# NewBee.net
KiCad netlist of a schematic drawn in Altium Designer
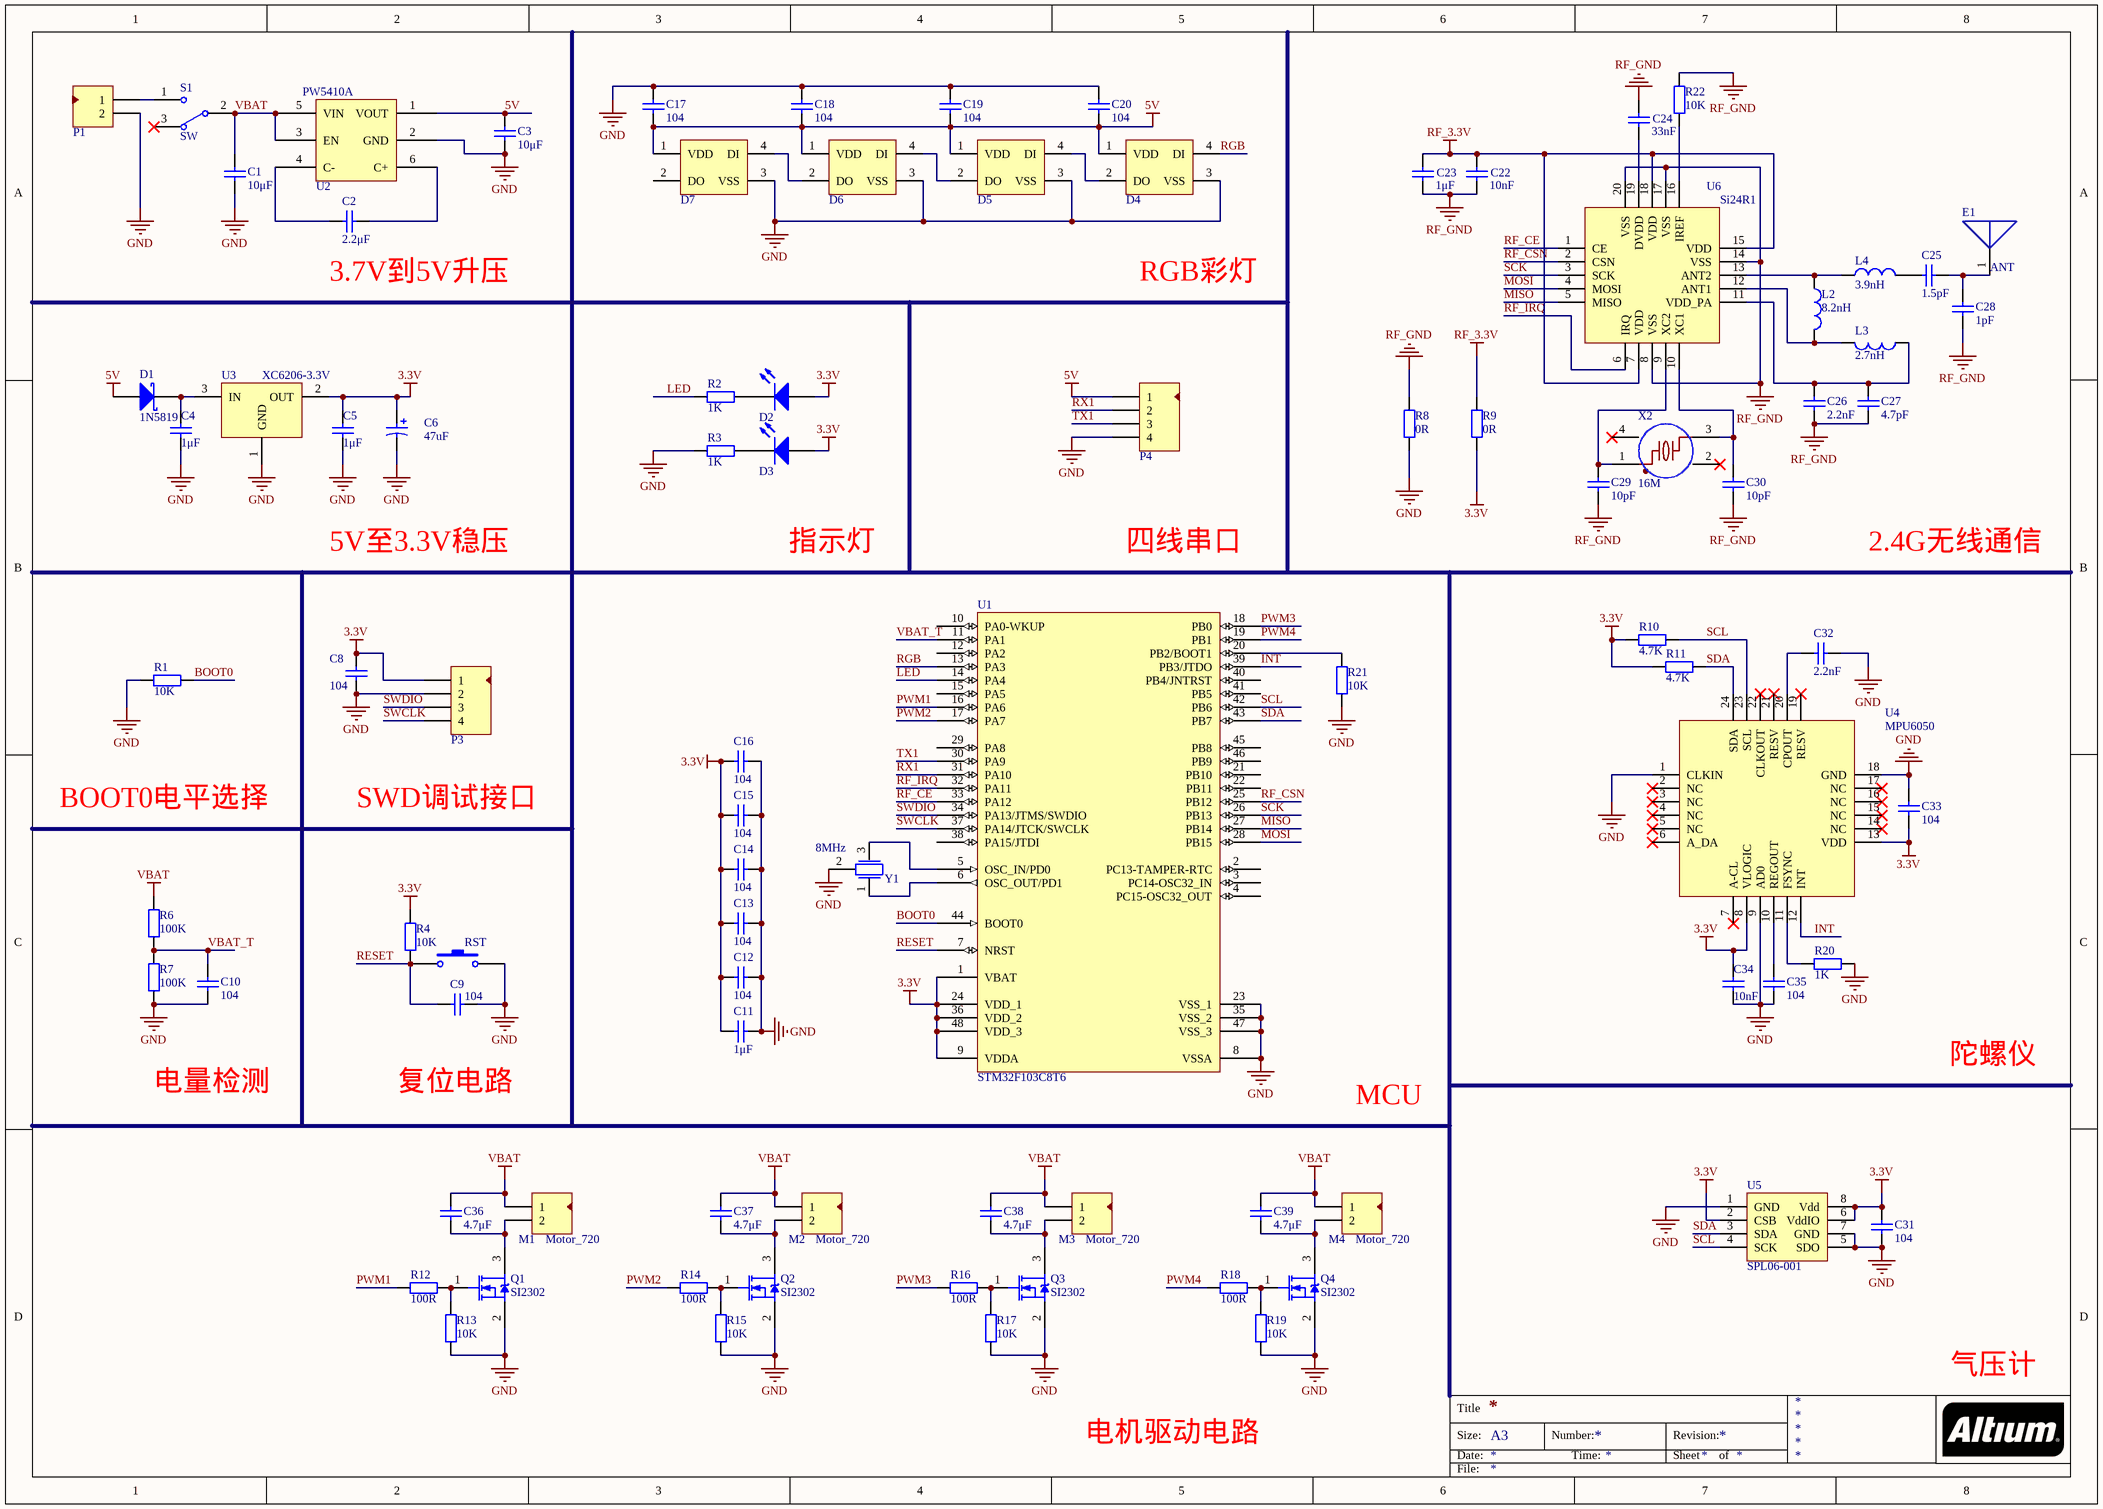
[diagram p0: NewBee.SchDoc]

(export (version "E")
  (design (tool "Eeschema 10.0.6"))
  (components
    (comp (ref "C1")
      (value "10μF")
      (footprint "C-0603")
      (description "贴片瓷片电容")
      (fields (field (name "PUBLISHER") "Altium Limited"))
      (libsource (lib "ChunLee") (part "Cap-S"))
    )
    (comp (ref "C2")
      (value "2.2μF")
      (footprint "C-0603")
      (description "贴片瓷片电容")
      (fields (field (name "PUBLISHER") "Altium Limited"))
      (libsource (lib "ChunLee") (part "Cap-S"))
    )
    (comp (ref "C3")
      (value "10μF")
      (footprint "C-0603")
      (description "贴片瓷片电容")
      (fields (field (name "PUBLISHER") "Altium Limited"))
      (libsource (lib "ChunLee") (part "Cap-S"))
    )
    (comp (ref "C4")
      (value "1μF")
      (footprint "C-0603")
      (description "贴片瓷片电容")
      (fields (field (name "PUBLISHER") "Altium Limited"))
      (libsource (lib "ChunLee") (part "Cap-S"))
    )
    (comp (ref "C5")
      (value "1μF")
      (footprint "C-0603")
      (description "贴片瓷片电容")
      (fields (field (name "PUBLISHER") "Altium Limited"))
      (libsource (lib "ChunLee") (part "Cap-S"))
    )
    (comp (ref "C6")
      (value "47uF")
      (footprint "CAP-3216")
      (description "钽电容")
      (fields (field (name "Comment") "Cap-Pol") (field (name "PUBLISHER") "Altium Limited"))
      (libsource (lib "ChunLee") (part "Cap-Pol-A"))
    )
    (comp (ref "C8")
      (value "104")
      (footprint "C-0603")
      (description "贴片瓷片电容")
      (fields (field (name "PUBLISHER") "Altium Limited"))
      (libsource (lib "ChunLee") (part "Cap-S"))
    )
    (comp (ref "C9")
      (value "104")
      (footprint "C-0603")
      (description "贴片瓷片电容")
      (fields (field (name "PUBLISHER") "Altium Limited"))
      (libsource (lib "ChunLee") (part "Cap-S"))
    )
    (comp (ref "C10")
      (value "104")
      (footprint "C-0603")
      (description "贴片瓷片电容")
      (fields (field (name "PUBLISHER") "Altium Limited"))
      (libsource (lib "ChunLee") (part "Cap-S"))
    )
    (comp (ref "C11")
      (value "1μF")
      (footprint "C-0603")
      (description "贴片瓷片电容")
      (fields (field (name "PUBLISHER") "Altium Limited"))
      (libsource (lib "ChunLee") (part "Cap-S"))
    )
    (comp (ref "C12")
      (value "104")
      (footprint "C-0603")
      (description "贴片瓷片电容")
      (fields (field (name "PUBLISHER") "Altium Limited"))
      (libsource (lib "ChunLee") (part "Cap-S"))
    )
    (comp (ref "C13")
      (value "104")
      (footprint "C-0603")
      (description "贴片瓷片电容")
      (fields (field (name "PUBLISHER") "Altium Limited"))
      (libsource (lib "ChunLee") (part "Cap-S"))
    )
    (comp (ref "C14")
      (value "104")
      (footprint "C-0603")
      (description "贴片瓷片电容")
      (fields (field (name "PUBLISHER") "Altium Limited"))
      (libsource (lib "ChunLee") (part "Cap-S"))
    )
    (comp (ref "C15")
      (value "104")
      (footprint "C-0603")
      (description "贴片瓷片电容")
      (fields (field (name "PUBLISHER") "Altium Limited"))
      (libsource (lib "ChunLee") (part "Cap-S"))
    )
    (comp (ref "C16")
      (value "104")
      (footprint "C-0603")
      (description "贴片瓷片电容")
      (fields (field (name "PUBLISHER") "Altium Limited"))
      (libsource (lib "ChunLee") (part "Cap-S"))
    )
    (comp (ref "C17")
      (value "104")
      (footprint "C-0603")
      (description "贴片瓷片电容")
      (fields (field (name "PUBLISHER") "Altium Limited"))
      (libsource (lib "ChunLee") (part "Cap-S"))
    )
    (comp (ref "C18")
      (value "104")
      (footprint "C-0603")
      (description "贴片瓷片电容")
      (fields (field (name "PUBLISHER") "Altium Limited"))
      (libsource (lib "ChunLee") (part "Cap-S"))
    )
    (comp (ref "C19")
      (value "104")
      (footprint "C-0603")
      (description "贴片瓷片电容")
      (fields (field (name "PUBLISHER") "Altium Limited"))
      (libsource (lib "ChunLee") (part "Cap-S"))
    )
    (comp (ref "C20")
      (value "104")
      (footprint "C-0603")
      (description "贴片瓷片电容")
      (fields (field (name "PUBLISHER") "Altium Limited"))
      (libsource (lib "ChunLee") (part "Cap-S"))
    )
    (comp (ref "C22")
      (value "10nF")
      (footprint "C-0603")
      (description "贴片瓷片电容")
      (fields (field (name "PUBLISHER") "Altium Limited"))
      (libsource (lib "ChunLee") (part "Cap-S"))
    )
    (comp (ref "C23")
      (value "1μF")
      (footprint "C-0603")
      (description "贴片瓷片电容")
      (fields (field (name "PUBLISHER") "Altium Limited"))
      (libsource (lib "ChunLee") (part "Cap-S"))
    )
    (comp (ref "C24")
      (value "33nF")
      (footprint "C-0603")
      (description "贴片瓷片电容")
      (fields (field (name "PUBLISHER") "Altium Limited"))
      (libsource (lib "ChunLee") (part "Cap-S"))
    )
    (comp (ref "C25")
      (value "1.5pF")
      (footprint "C-0603")
      (description "贴片瓷片电容")
      (fields (field (name "PUBLISHER") "Altium Limited"))
      (libsource (lib "ChunLee") (part "Cap-S"))
    )
    (comp (ref "C26")
      (value "2.2nF")
      (footprint "C-0603")
      (description "贴片瓷片电容")
      (fields (field (name "PUBLISHER") "Altium Limited"))
      (libsource (lib "ChunLee") (part "Cap-S"))
    )
    (comp (ref "C27")
      (value "4.7pF")
      (footprint "C-0603")
      (description "贴片瓷片电容")
      (fields (field (name "PUBLISHER") "Altium Limited"))
      (libsource (lib "ChunLee") (part "Cap-S"))
    )
    (comp (ref "C28")
      (value "1pF")
      (footprint "C-0603")
      (description "贴片瓷片电容")
      (fields (field (name "PUBLISHER") "Altium Limited"))
      (libsource (lib "ChunLee") (part "Cap-S"))
    )
    (comp (ref "C29")
      (value "10pF")
      (footprint "C-0603")
      (description "贴片瓷片电容")
      (fields (field (name "PUBLISHER") "Altium Limited"))
      (libsource (lib "ChunLee") (part "Cap-S"))
    )
    (comp (ref "C30")
      (value "10pF")
      (footprint "C-0603")
      (description "贴片瓷片电容")
      (fields (field (name "PUBLISHER") "Altium Limited"))
      (libsource (lib "ChunLee") (part "Cap-S"))
    )
    (comp (ref "C31")
      (value "104")
      (footprint "C-0603")
      (description "贴片瓷片电容")
      (fields (field (name "PUBLISHER") "Altium Limited"))
      (libsource (lib "ChunLee") (part "Cap-S"))
    )
    (comp (ref "C32")
      (value "2.2nF")
      (footprint "C-0603")
      (description "贴片瓷片电容")
      (fields (field (name "PUBLISHER") "Altium Limited"))
      (libsource (lib "ChunLee") (part "Cap-S"))
    )
    (comp (ref "C33")
      (value "104")
      (footprint "C-0603")
      (description "贴片瓷片电容")
      (fields (field (name "PUBLISHER") "Altium Limited"))
      (libsource (lib "ChunLee") (part "Cap-S"))
    )
    (comp (ref "C34")
      (value "10nF")
      (footprint "C-0603")
      (description "贴片瓷片电容")
      (fields (field (name "PUBLISHER") "Altium Limited"))
      (libsource (lib "ChunLee") (part "Cap-S"))
    )
    (comp (ref "C35")
      (value "104")
      (footprint "C-0603")
      (description "贴片瓷片电容")
      (fields (field (name "PUBLISHER") "Altium Limited"))
      (libsource (lib "ChunLee") (part "Cap-S"))
    )
    (comp (ref "C36")
      (value "4.7μF")
      (footprint "C-0603")
      (description "贴片瓷片电容")
      (fields (field (name "PUBLISHER") "Altium Limited"))
      (libsource (lib "ChunLee") (part "Cap-S"))
    )
    (comp (ref "C37")
      (value "4.7μF")
      (footprint "C-0603")
      (description "贴片瓷片电容")
      (fields (field (name "PUBLISHER") "Altium Limited"))
      (libsource (lib "ChunLee") (part "Cap-S"))
    )
    (comp (ref "C38")
      (value "4.7μF")
      (footprint "C-0603")
      (description "贴片瓷片电容")
      (fields (field (name "PUBLISHER") "Altium Limited"))
      (libsource (lib "ChunLee") (part "Cap-S"))
    )
    (comp (ref "C39")
      (value "4.7μF")
      (footprint "C-0603")
      (description "贴片瓷片电容")
      (fields (field (name "PUBLISHER") "Altium Limited"))
      (libsource (lib "ChunLee") (part "Cap-S"))
    )
    (comp (ref "D1")
      (value "1N5819")
      (footprint "SOD-323_L1.6-W1.3-LS2.7-RD")
      (description "肖特基二极管")
      (fields (field (name "TYPE") "1N5819") (field (name "PUBLISHER") "Altium Limited"))
      (libsource (lib "ChunLee") (part "Diode-Schottky"))
    )
    (comp (ref "D2")
      (value "LED0")
      (footprint "LED-0805")
      (description "发光二极管")
      (fields (field (name "PUBLISHER") "Altium Limited"))
      (libsource (lib "ChunLee") (part "LED0"))
    )
    (comp (ref "D3")
      (value "LED0")
      (footprint "LED-0805")
      (description "发光二极管")
      (fields (field (name "PUBLISHER") "Altium Limited"))
      (libsource (lib "ChunLee") (part "LED0"))
    )
    (comp (ref "D4")
      (value "WS2812B")
      (footprint "SMD-5050-4")
      (description "WS2812B 4脚RGB全彩LED")
      (libsource (lib "ChunLee") (part "WS2812B"))
    )
    (comp (ref "D5")
      (value "WS2812B")
      (footprint "SMD-5050-4")
      (description "WS2812B 4脚RGB全彩LED")
      (libsource (lib "ChunLee") (part "WS2812B"))
    )
    (comp (ref "D6")
      (value "WS2812B")
      (footprint "SMD-5050-4")
      (description "WS2812B 4脚RGB全彩LED")
      (libsource (lib "ChunLee") (part "WS2812B"))
    )
    (comp (ref "D7")
      (value "WS2812B")
      (footprint "SMD-5050-4")
      (description "WS2812B 4脚RGB全彩LED")
      (libsource (lib "ChunLee") (part "WS2812B"))
    )
    (comp (ref "E1")
      (value "ANT")
      (footprint "NewBee_PcbLib:AN3216")
      (description "2.4G Antenna")
      (fields (field (name "PUBLISHER") "mazhongwei"))
      (libsource (lib "NewBee_Schlib") (part "ANT"))
    )
    (comp (ref "L2")
      (value "8.2nH")
      (footprint "0603-1")
      (description "电感")
      (fields (field (name "Comment") "Inductor") (field (name "PUBLISHER") "Altium Limited"))
      (libsource (lib "ChunLee") (part "Inductor"))
    )
    (comp (ref "L3")
      (value "2.7nH")
      (footprint "0603-1")
      (description "电感")
      (fields (field (name "Comment") "Inductor") (field (name "PUBLISHER") "Altium Limited"))
      (libsource (lib "ChunLee") (part "Inductor"))
    )
    (comp (ref "L4")
      (value "3.9nH")
      (footprint "0603-1")
      (description "电感")
      (fields (field (name "Comment") "Inductor") (field (name "PUBLISHER") "Altium Limited"))
      (libsource (lib "ChunLee") (part "Inductor"))
    )
    (comp (ref "M1")
      (value "Motor_720")
      (footprint "PH2.0-2P-TH")
      (description "接插件")
      (fields (field (name "PUBLISHER") "Altium Limited"))
      (libsource (lib "HDR_ChunLee") (part "Header 2"))
    )
    (comp (ref "M2")
      (value "Motor_720")
      (footprint "PH2.0-2P-TH")
      (description "接插件")
      (fields (field (name "PUBLISHER") "Altium Limited"))
      (libsource (lib "HDR_ChunLee") (part "Header 2"))
    )
    (comp (ref "M3")
      (value "Motor_720")
      (footprint "PH2.0-2P-TH")
      (description "接插件")
      (fields (field (name "PUBLISHER") "Altium Limited"))
      (libsource (lib "HDR_ChunLee") (part "Header 2"))
    )
    (comp (ref "M4")
      (value "Motor_720")
      (footprint "PH2.0-2P-TH")
      (description "接插件")
      (fields (field (name "PUBLISHER") "Altium Limited"))
      (libsource (lib "HDR_ChunLee") (part "Header 2"))
    )
    (comp (ref "P1")
      (value "Header 2")
      (footprint "51005")
      (description "接插件")
      (fields (field (name "PUBLISHER") "Altium Limited"))
      (libsource (lib "") (part "Header 2_1"))
    )
    (comp (ref "P3")
      (value "Header 4")
      (footprint "HDR4X1-2.54")
      (description "接插件")
      (fields (field (name "PUBLISHER") "Altium Limited"))
      (libsource (lib "HDR_ChunLee") (part "Header 4"))
    )
    (comp (ref "P4")
      (value "Header 4")
      (footprint "HDR4X1-2.54")
      (description "接插件")
      (fields (field (name "PUBLISHER") "Altium Limited"))
      (libsource (lib "HDR_ChunLee") (part "Header 4"))
    )
    (comp (ref "Q1")
      (value "SI2302")
      (footprint "SOT23-3")
      (description "N沟道贴片")
      (fields (field (name "PUBLISHER") "Altium Limited"))
      (libsource (lib "ChunLee") (part "SI2302"))
    )
    (comp (ref "Q2")
      (value "SI2302")
      (footprint "SOT23-3")
      (description "N沟道贴片")
      (fields (field (name "PUBLISHER") "Altium Limited"))
      (libsource (lib "ChunLee") (part "SI2302"))
    )
    (comp (ref "Q3")
      (value "SI2302")
      (footprint "SOT23-3")
      (description "N沟道贴片")
      (fields (field (name "PUBLISHER") "Altium Limited"))
      (libsource (lib "ChunLee") (part "SI2302"))
    )
    (comp (ref "Q4")
      (value "SI2302")
      (footprint "SOT23-3")
      (description "N沟道贴片")
      (fields (field (name "PUBLISHER") "Altium Limited"))
      (libsource (lib "ChunLee") (part "SI2302"))
    )
    (comp (ref "R1")
      (value "10K")
      (footprint "0603-1")
      (description "贴片电阻")
      (fields (field (name "PUBLISHER") "Altium Limited"))
      (libsource (lib "") (part "Res1_3"))
    )
    (comp (ref "R2")
      (value "1K")
      (footprint "0603-1")
      (description "贴片电阻")
      (fields (field (name "PUBLISHER") "Altium Limited"))
      (libsource (lib "") (part "Res1_2"))
    )
    (comp (ref "R3")
      (value "1K")
      (footprint "0603-1")
      (description "贴片电阻")
      (fields (field (name "PUBLISHER") "Altium Limited"))
      (libsource (lib "") (part "Res1_2"))
    )
    (comp (ref "R4")
      (value "10K")
      (footprint "0603-1")
      (description "贴片电阻")
      (fields (field (name "PUBLISHER") "Altium Limited"))
      (libsource (lib "") (part "Res1_1"))
    )
    (comp (ref "R6")
      (value "100K")
      (footprint "0603-1")
      (description "贴片电阻")
      (fields (field (name "PUBLISHER") "Altium Limited"))
      (libsource (lib "ChunLee") (part "Res1"))
    )
    (comp (ref "R7")
      (value "100K")
      (footprint "0603-1")
      (description "贴片电阻")
      (fields (field (name "PUBLISHER") "Altium Limited"))
      (libsource (lib "ChunLee") (part "Res1"))
    )
    (comp (ref "R8")
      (value "0R")
      (footprint "0603-1")
      (description "贴片电阻")
      (fields (field (name "PUBLISHER") "Altium Limited"))
      (libsource (lib "ChunLee") (part "Res1"))
    )
    (comp (ref "R9")
      (value "0R")
      (footprint "0603-1")
      (description "贴片电阻")
      (fields (field (name "PUBLISHER") "Altium Limited"))
      (libsource (lib "ChunLee") (part "Res1"))
    )
    (comp (ref "R10")
      (value "4.7K")
      (footprint "0603-1")
      (description "贴片电阻")
      (fields (field (name "PUBLISHER") "Altium Limited"))
      (libsource (lib "") (part "Res1_2"))
    )
    (comp (ref "R11")
      (value "4.7K")
      (footprint "0603-1")
      (description "贴片电阻")
      (fields (field (name "PUBLISHER") "Altium Limited"))
      (libsource (lib "") (part "Res1_2"))
    )
    (comp (ref "R12")
      (value "100R")
      (footprint "0603-1")
      (description "贴片电阻")
      (fields (field (name "PUBLISHER") "Altium Limited"))
      (libsource (lib "") (part "Res1_2"))
    )
    (comp (ref "R13")
      (value "10K")
      (footprint "0603-1")
      (description "贴片电阻")
      (fields (field (name "PUBLISHER") "Altium Limited"))
      (libsource (lib "") (part "Res1_1"))
    )
    (comp (ref "R14")
      (value "100R")
      (footprint "0603-1")
      (description "贴片电阻")
      (fields (field (name "PUBLISHER") "Altium Limited"))
      (libsource (lib "") (part "Res1_2"))
    )
    (comp (ref "R15")
      (value "10K")
      (footprint "0603-1")
      (description "贴片电阻")
      (fields (field (name "PUBLISHER") "Altium Limited"))
      (libsource (lib "") (part "Res1_1"))
    )
    (comp (ref "R16")
      (value "100R")
      (footprint "0603-1")
      (description "贴片电阻")
      (fields (field (name "PUBLISHER") "Altium Limited"))
      (libsource (lib "") (part "Res1_2"))
    )
    (comp (ref "R17")
      (value "10K")
      (footprint "0603-1")
      (description "贴片电阻")
      (fields (field (name "PUBLISHER") "Altium Limited"))
      (libsource (lib "") (part "Res1_1"))
    )
    (comp (ref "R18")
      (value "100R")
      (footprint "0603-1")
      (description "贴片电阻")
      (fields (field (name "PUBLISHER") "Altium Limited"))
      (libsource (lib "") (part "Res1_2"))
    )
    (comp (ref "R19")
      (value "10K")
      (footprint "0603-1")
      (description "贴片电阻")
      (fields (field (name "PUBLISHER") "Altium Limited"))
      (libsource (lib "") (part "Res1_1"))
    )
    (comp (ref "R20")
      (value "1K")
      (footprint "0603-1")
      (description "贴片电阻")
      (fields (field (name "PUBLISHER") "Altium Limited"))
      (libsource (lib "") (part "Res1_3"))
    )
    (comp (ref "R21")
      (value "10K")
      (footprint "0603-1")
      (description "贴片电阻")
      (fields (field (name "PUBLISHER") "Altium Limited"))
      (libsource (lib "ChunLee") (part "Res1"))
    )
    (comp (ref "R22")
      (value "10K")
      (footprint "0603-1")
      (description "贴片电阻")
      (fields (field (name "PUBLISHER") "Altium Limited"))
      (libsource (lib "ChunLee") (part "Res1"))
    )
    (comp (ref "RST")
      (value "SW-PB")
      (footprint "SW-SMD_L4.0-W3.0-P4.8-LS5.0-L")
      (description "微动开关")
      (fields (field (name "PUBLISHER") "Altium Limited"))
      (libsource (lib "ChunLee") (part "SW-PB"))
    )
    (comp (ref "S1")
      (value "SW")
      (footprint "SW-SMD_DEALON_MK-12D04-G2")
      (description "开关")
      (fields (field (name "PUBLISHER") "Altium Limited"))
      (libsource (lib "ChunLee") (part "SW-SPDT"))
    )
    (comp (ref "U1")
      (value "STM32F103C8T6")
      (footprint "LQFP-48")
      (description "STM32F103, 48引脚, 64Kb Flash, 20Kb SRAM")
      (fields (field (name "PUBLISHER") "Altium Limited"))
      (libsource (lib "ChunLee") (part "STM32F103C8T6"))
    )
    (comp (ref "U2")
      (value "PW5410A")
      (footprint "SOT23-6")
      (description "5V/3.3V升压芯片")
      (libsource (lib "ChunLee") (part "PW5410A/B"))
    )
    (comp (ref "U3")
      (value "XC6206-3.3V")
      (footprint "SOT23-3")
      (description "稳压芯片")
      (libsource (lib "ChunLee") (part "XC6206"))
    )
    (comp (ref "U4") (value "MPU6050") (footprint "QFN-24") (libsource (lib "ChunLee") (part "MPU6050")))
    (comp (ref "U5")
      (value "SPL06-001")
      (footprint "SENSOR-SMD_SPL06-001")
      (description "气压计")
      (fields (field (name "PUBLISHER") "mazhongwei"))
      (libsource (lib "NewBee_Schlib") (part "FBM320"))
    )
    (comp (ref "U6") (value "Si24R1") (footprint "QFN20") (libsource (lib "NewBee_Schlib") (part "nRF24L01")))
    (comp (ref "X2")
      (value "16M")
      (footprint "X-SMD_4P-L3.2-W2.5-BL")
      (libsource (lib "ChunLee") (part "XTAL-4PIN"))
    )
    (comp (ref "Y1")
      (value "8MHz")
      (footprint "OSC-SMD_3P-L3.2-W1.3-P1.20-L")
      (description "贴片晶振")
      (libsource (lib "ChunLee") (part "XTAL-3PIN"))
    )
  )
  (nets
    (net (code "1") (name "/BOOT0") (class "Default")
      (node (ref "R1") (pin "1") (pinfunction "1_1") (pintype "passive"))
      (node (ref "U1") (pin "44") (pinfunction "BOOT0_44") (pintype "input"))
    )
    (net (code "2") (name "/INT") (class "Default")
      (node (ref "U1") (pin "39") (pinfunction "PB3/JTDO_39") (pintype "bidirectional"))
      (node (ref "U4") (pin "12") (pinfunction "INT_12") (pintype "passive"))
    )
    (net (code "3") (name "/LED") (class "Default")
      (node (ref "R2") (pin "1") (pinfunction "1_1") (pintype "passive"))
      (node (ref "U1") (pin "14") (pinfunction "PA4_14") (pintype "bidirectional"))
    )
    (net (code "4") (name "/MISO") (class "Default")
      (node (ref "U1") (pin "27") (pinfunction "PB14_27") (pintype "bidirectional"))
      (node (ref "U6") (pin "5") (pinfunction "MISO_5") (pintype "passive"))
    )
    (net (code "5") (name "/MOSI") (class "Default")
      (node (ref "U1") (pin "28") (pinfunction "PB15_28") (pintype "bidirectional"))
      (node (ref "U6") (pin "4") (pinfunction "MOSI_4") (pintype "passive"))
    )
    (net (code "6") (name "/PWM1") (class "Default")
      (node (ref "R12") (pin "1") (pinfunction "1_1") (pintype "passive"))
      (node (ref "U1") (pin "16") (pinfunction "PA6_16") (pintype "bidirectional"))
    )
    (net (code "7") (name "/PWM2") (class "Default")
      (node (ref "R14") (pin "1") (pinfunction "1_1") (pintype "passive"))
      (node (ref "U1") (pin "17") (pinfunction "PA7_17") (pintype "bidirectional"))
    )
    (net (code "8") (name "/PWM3") (class "Default")
      (node (ref "R16") (pin "1") (pinfunction "1_1") (pintype "passive"))
      (node (ref "U1") (pin "18") (pinfunction "PB0_18") (pintype "bidirectional"))
    )
    (net (code "9") (name "/PWM4") (class "Default")
      (node (ref "R18") (pin "1") (pinfunction "1_1") (pintype "passive"))
      (node (ref "U1") (pin "19") (pinfunction "PB1_19") (pintype "bidirectional"))
    )
    (net (code "10") (name "/RESET") (class "Default")
      (node (ref "C9") (pin "1") (pinfunction "1_1") (pintype "passive"))
      (node (ref "R4") (pin "1") (pinfunction "1_1") (pintype "passive"))
      (node (ref "RST") (pin "1") (pinfunction "1_1") (pintype "passive"))
      (node (ref "U1") (pin "7") (pinfunction "NRST_7") (pintype "bidirectional"))
    )
    (net (code "11") (name "/RF_CE") (class "Default")
      (node (ref "U1") (pin "33") (pinfunction "PA12_33") (pintype "bidirectional"))
      (node (ref "U6") (pin "1") (pinfunction "CE_1") (pintype "passive"))
    )
    (net (code "12") (name "/RF_CSN") (class "Default")
      (node (ref "U1") (pin "25") (pinfunction "PB12_25") (pintype "bidirectional"))
      (node (ref "U6") (pin "2") (pinfunction "CSN_2") (pintype "passive"))
    )
    (net (code "13") (name "/RF_IRQ") (class "Default")
      (node (ref "U1") (pin "32") (pinfunction "PA11_32") (pintype "bidirectional"))
      (node (ref "U6") (pin "6") (pinfunction "IRQ_6") (pintype "passive"))
    )
    (net (code "14") (name "/RGB") (class "Default")
      (node (ref "D4") (pin "4") (pinfunction "DI_4") (pintype "passive"))
      (node (ref "U1") (pin "13") (pinfunction "PA3_13") (pintype "bidirectional"))
    )
    (net (code "15") (name "/RX1") (class "Default")
      (node (ref "P4") (pin "2") (pinfunction "2_2") (pintype "passive"))
      (node (ref "U1") (pin "31") (pinfunction "PA10_31") (pintype "bidirectional"))
    )
    (net (code "16") (name "/SCK") (class "Default")
      (node (ref "U1") (pin "26") (pinfunction "PB13_26") (pintype "bidirectional"))
      (node (ref "U6") (pin "3") (pinfunction "SCK_3") (pintype "passive"))
    )
    (net (code "17") (name "/SCL") (class "Default")
      (node (ref "R10") (pin "2") (pinfunction "2_2") (pintype "passive"))
      (node (ref "U1") (pin "42") (pinfunction "PB6_42") (pintype "bidirectional"))
      (node (ref "U4") (pin "23") (pinfunction "SCL_23") (pintype "passive"))
      (node (ref "U5") (pin "4") (pinfunction "SCK_4") (pintype "passive"))
    )
    (net (code "18") (name "/SDA") (class "Default")
      (node (ref "R11") (pin "2") (pinfunction "2_2") (pintype "passive"))
      (node (ref "U1") (pin "43") (pinfunction "PB7_43") (pintype "bidirectional"))
      (node (ref "U4") (pin "24") (pinfunction "SDA_24") (pintype "passive"))
      (node (ref "U5") (pin "3") (pinfunction "SDA_3") (pintype "passive"))
    )
    (net (code "19") (name "/SWCLK") (class "Default")
      (node (ref "P3") (pin "4") (pinfunction "4_4") (pintype "passive"))
      (node (ref "U1") (pin "37") (pinfunction "PA14/JTCK/SWCLK_37") (pintype "bidirectional"))
    )
    (net (code "20") (name "/SWDIO") (class "Default")
      (node (ref "P3") (pin "3") (pinfunction "3_3") (pintype "passive"))
      (node (ref "U1") (pin "34") (pinfunction "PA13/JTMS/SWDIO_34") (pintype "bidirectional"))
    )
    (net (code "21") (name "/TX1") (class "Default")
      (node (ref "P4") (pin "3") (pinfunction "3_3") (pintype "passive"))
      (node (ref "U1") (pin "30") (pinfunction "PA9_30") (pintype "bidirectional"))
    )
    (net (code "22") (name "/VBAT_T") (class "Default")
      (node (ref "C10") (pin "2") (pinfunction "2_2") (pintype "passive"))
      (node (ref "R6") (pin "2") (pinfunction "2_2") (pintype "passive"))
      (node (ref "R7") (pin "1") (pinfunction "1_1") (pintype "passive"))
      (node (ref "U1") (pin "11") (pinfunction "PA1_11") (pintype "bidirectional"))
    )
    (net (code "23") (name "3.3V") (class "Default")
      (node (ref "C11") (pin "2") (pinfunction "2_2") (pintype "passive"))
      (node (ref "C12") (pin "2") (pinfunction "2_2") (pintype "passive"))
      (node (ref "C13") (pin "2") (pinfunction "2_2") (pintype "passive"))
      (node (ref "C14") (pin "1") (pinfunction "1_1") (pintype "passive"))
      (node (ref "C15") (pin "2") (pinfunction "2_2") (pintype "passive"))
      (node (ref "C16") (pin "2") (pinfunction "2_2") (pintype "passive"))
      (node (ref "C31") (pin "2") (pinfunction "2_2") (pintype "passive"))
      (node (ref "C33") (pin "2") (pinfunction "2_2") (pintype "passive"))
      (node (ref "C34") (pin "2") (pinfunction "2_2") (pintype "passive"))
      (node (ref "C5") (pin "1") (pinfunction "1_1") (pintype "passive"))
      (node (ref "C6") (pin "1") (pinfunction "1_1") (pintype "passive"))
      (node (ref "C8") (pin "1") (pinfunction "1_1") (pintype "passive"))
      (node (ref "D2") (pin "1") (pinfunction "A_1") (pintype "passive"))
      (node (ref "D3") (pin "1") (pinfunction "A_1") (pintype "passive"))
      (node (ref "P3") (pin "1") (pinfunction "1_1") (pintype "passive"))
      (node (ref "R10") (pin "1") (pinfunction "1_1") (pintype "passive"))
      (node (ref "R11") (pin "1") (pinfunction "1_1") (pintype "passive"))
      (node (ref "R4") (pin "2") (pinfunction "2_2") (pintype "passive"))
      (node (ref "R9") (pin "2") (pinfunction "2_2") (pintype "passive"))
      (node (ref "U1") (pin "1") (pinfunction "VBAT_1") (pintype "power_in"))
      (node (ref "U1") (pin "24") (pinfunction "VDD_1_24") (pintype "power_in"))
      (node (ref "U1") (pin "36") (pinfunction "VDD_2_36") (pintype "power_in"))
      (node (ref "U1") (pin "48") (pinfunction "VDD_3_48") (pintype "power_in"))
      (node (ref "U1") (pin "9") (pinfunction "VDDA_9") (pintype "power_in"))
      (node (ref "U3") (pin "2") (pinfunction "OUT_2") (pintype "passive"))
      (node (ref "U4") (pin "13") (pinfunction "VDD_13") (pintype "passive"))
      (node (ref "U4") (pin "8") (pinfunction "VLOGIC_8") (pintype "passive"))
      (node (ref "U5") (pin "2") (pinfunction "CSB_2") (pintype "passive"))
      (node (ref "U5") (pin "6") (pinfunction "VddIO_6") (pintype "passive"))
      (node (ref "U5") (pin "8") (pinfunction "Vdd_8") (pintype "passive"))
    )
    (net (code "24") (name "5V") (class "Default")
      (node (ref "C17") (pin "1") (pinfunction "1_1") (pintype "passive"))
      (node (ref "C18") (pin "1") (pinfunction "1_1") (pintype "passive"))
      (node (ref "C19") (pin "1") (pinfunction "1_1") (pintype "passive"))
      (node (ref "C20") (pin "1") (pinfunction "1_1") (pintype "passive"))
      (node (ref "C3") (pin "2") (pinfunction "2_2") (pintype "passive"))
      (node (ref "D1") (pin "1") (pinfunction "A_1") (pintype "passive"))
      (node (ref "D4") (pin "1") (pinfunction "VDD_1") (pintype "passive"))
      (node (ref "D5") (pin "1") (pinfunction "VDD_1") (pintype "passive"))
      (node (ref "D6") (pin "1") (pinfunction "VDD_1") (pintype "passive"))
      (node (ref "D7") (pin "1") (pinfunction "VDD_1") (pintype "passive"))
      (node (ref "P4") (pin "1") (pinfunction "1_1") (pintype "passive"))
      (node (ref "U2") (pin "1") (pinfunction "VOUT_1") (pintype "passive"))
    )
    (net (code "25") (name "GND") (class "Default")
      (node (ref "C1") (pin "1") (pinfunction "1_1") (pintype "passive"))
      (node (ref "C10") (pin "1") (pinfunction "1_1") (pintype "passive"))
      (node (ref "C11") (pin "1") (pinfunction "1_1") (pintype "passive"))
      (node (ref "C12") (pin "1") (pinfunction "1_1") (pintype "passive"))
      (node (ref "C13") (pin "1") (pinfunction "1_1") (pintype "passive"))
      (node (ref "C14") (pin "2") (pinfunction "2_2") (pintype "passive"))
      (node (ref "C15") (pin "1") (pinfunction "1_1") (pintype "passive"))
      (node (ref "C16") (pin "1") (pinfunction "1_1") (pintype "passive"))
      (node (ref "C17") (pin "2") (pinfunction "2_2") (pintype "passive"))
      (node (ref "C18") (pin "2") (pinfunction "2_2") (pintype "passive"))
      (node (ref "C19") (pin "2") (pinfunction "2_2") (pintype "passive"))
      (node (ref "C20") (pin "2") (pinfunction "2_2") (pintype "passive"))
      (node (ref "C3") (pin "1") (pinfunction "1_1") (pintype "passive"))
      (node (ref "C31") (pin "1") (pinfunction "1_1") (pintype "passive"))
      (node (ref "C32") (pin "1") (pinfunction "1_1") (pintype "passive"))
      (node (ref "C33") (pin "1") (pinfunction "1_1") (pintype "passive"))
      (node (ref "C34") (pin "1") (pinfunction "1_1") (pintype "passive"))
      (node (ref "C35") (pin "2") (pinfunction "2_2") (pintype "passive"))
      (node (ref "C4") (pin "2") (pinfunction "2_2") (pintype "passive"))
      (node (ref "C5") (pin "2") (pinfunction "2_2") (pintype "passive"))
      (node (ref "C6") (pin "2") (pinfunction "2_2") (pintype "passive"))
      (node (ref "C8") (pin "2") (pinfunction "2_2") (pintype "passive"))
      (node (ref "C9") (pin "2") (pinfunction "2_2") (pintype "passive"))
      (node (ref "D4") (pin "3") (pinfunction "VSS_3") (pintype "passive"))
      (node (ref "D5") (pin "3") (pinfunction "VSS_3") (pintype "passive"))
      (node (ref "D6") (pin "3") (pinfunction "VSS_3") (pintype "passive"))
      (node (ref "D7") (pin "3") (pinfunction "VSS_3") (pintype "passive"))
      (node (ref "P1") (pin "2") (pinfunction "2_2") (pintype "passive"))
      (node (ref "P3") (pin "2") (pinfunction "2_2") (pintype "passive"))
      (node (ref "P4") (pin "4") (pinfunction "4_4") (pintype "passive"))
      (node (ref "Q1") (pin "2") (pinfunction "S_2") (pintype "passive"))
      (node (ref "Q2") (pin "2") (pinfunction "S_2") (pintype "passive"))
      (node (ref "Q3") (pin "2") (pinfunction "S_2") (pintype "passive"))
      (node (ref "Q4") (pin "2") (pinfunction "S_2") (pintype "passive"))
      (node (ref "R1") (pin "2") (pinfunction "2_2") (pintype "passive"))
      (node (ref "R13") (pin "1") (pinfunction "1_1") (pintype "passive"))
      (node (ref "R15") (pin "1") (pinfunction "1_1") (pintype "passive"))
      (node (ref "R17") (pin "1") (pinfunction "1_1") (pintype "passive"))
      (node (ref "R19") (pin "1") (pinfunction "1_1") (pintype "passive"))
      (node (ref "R20") (pin "1") (pinfunction "1_1") (pintype "passive"))
      (node (ref "R21") (pin "2") (pinfunction "2_2") (pintype "passive"))
      (node (ref "R3") (pin "1") (pinfunction "1_1") (pintype "passive"))
      (node (ref "R7") (pin "2") (pinfunction "2_2") (pintype "passive"))
      (node (ref "R8") (pin "2") (pinfunction "2_2") (pintype "passive"))
      (node (ref "RST") (pin "2") (pinfunction "2_2") (pintype "passive"))
      (node (ref "U1") (pin "23") (pinfunction "VSS_1_23") (pintype "power_in"))
      (node (ref "U1") (pin "35") (pinfunction "VSS_2_35") (pintype "power_in"))
      (node (ref "U1") (pin "47") (pinfunction "VSS_3_47") (pintype "power_in"))
      (node (ref "U1") (pin "8") (pinfunction "VSSA_8") (pintype "power_in"))
      (node (ref "U2") (pin "2") (pinfunction "GND_2") (pintype "passive"))
      (node (ref "U3") (pin "1") (pinfunction "GND_1") (pintype "passive"))
      (node (ref "U4") (pin "1") (pinfunction "CLKIN_1") (pintype "passive"))
      (node (ref "U4") (pin "18") (pinfunction "GND_18") (pintype "passive"))
      (node (ref "U4") (pin "9") (pinfunction "AD0_9") (pintype "passive"))
      (node (ref "U5") (pin "1") (pinfunction "GND_1") (pintype "passive"))
      (node (ref "U5") (pin "5") (pinfunction "SDO_5") (pintype "passive"))
      (node (ref "U5") (pin "7") (pinfunction "GND_7") (pintype "passive"))
      (node (ref "Y1") (pin "2") (pinfunction "2_2") (pintype "passive"))
    )
    (net (code "26") (name "Net-(C25-Pad1)") (class "Default")
      (node (ref "C25") (pin "1") (pinfunction "1_1") (pintype "passive"))
      (node (ref "C28") (pin "2") (pinfunction "2_2") (pintype "passive"))
      (node (ref "E1") (pin "1") (pinfunction "1_1") (pintype "passive"))
    )
    (net (code "27") (name "Net-(C25-Pad2)") (class "Default")
      (node (ref "C25") (pin "2") (pinfunction "2_2") (pintype "passive"))
      (node (ref "L4") (pin "2") (pinfunction "2_2") (pintype "passive"))
    )
    (net (code "28") (name "Net-(D1-K)") (class "Default")
      (node (ref "C4") (pin "1") (pinfunction "1_1") (pintype "passive"))
      (node (ref "D1") (pin "2") (pinfunction "K_2") (pintype "passive"))
      (node (ref "U3") (pin "3") (pinfunction "IN_3") (pintype "passive"))
    )
    (net (code "29") (name "Net-(D2-K)") (class "Default")
      (node (ref "D2") (pin "2") (pinfunction "K_2") (pintype "passive"))
      (node (ref "R2") (pin "2") (pinfunction "2_2") (pintype "passive"))
    )
    (net (code "30") (name "Net-(D3-K)") (class "Default")
      (node (ref "D3") (pin "2") (pinfunction "K_2") (pintype "passive"))
      (node (ref "R3") (pin "2") (pinfunction "2_2") (pintype "passive"))
    )
    (net (code "31") (name "Net-(D4-DO)") (class "Default")
      (node (ref "D4") (pin "2") (pinfunction "DO_2") (pintype "passive"))
      (node (ref "D5") (pin "4") (pinfunction "DI_4") (pintype "passive"))
    )
    (net (code "32") (name "Net-(D5-DO)") (class "Default")
      (node (ref "D5") (pin "2") (pinfunction "DO_2") (pintype "passive"))
      (node (ref "D6") (pin "4") (pinfunction "DI_4") (pintype "passive"))
    )
    (net (code "33") (name "Net-(D6-DO)") (class "Default")
      (node (ref "D6") (pin "2") (pinfunction "DO_2") (pintype "passive"))
      (node (ref "D7") (pin "4") (pinfunction "DI_4") (pintype "passive"))
    )
    (net (code "34") (name "Net-(P1-Pad1)") (class "Default")
      (node (ref "P1") (pin "1") (pinfunction "1_1") (pintype "passive"))
      (node (ref "S1") (pin "1") (pinfunction "1_1") (pintype "passive"))
    )
    (net (code "35") (name "Net-(Q1-D)") (class "Default")
      (node (ref "C36") (pin "2") (pinfunction "2_2") (pintype "passive"))
      (node (ref "M1") (pin "2") (pinfunction "2_2") (pintype "passive"))
      (node (ref "Q1") (pin "3") (pinfunction "D_3") (pintype "passive"))
    )
    (net (code "36") (name "Net-(Q1-G)") (class "Default")
      (node (ref "Q1") (pin "1") (pinfunction "G_1") (pintype "passive"))
      (node (ref "R12") (pin "2") (pinfunction "2_2") (pintype "passive"))
      (node (ref "R13") (pin "2") (pinfunction "2_2") (pintype "passive"))
    )
    (net (code "37") (name "Net-(Q2-D)") (class "Default")
      (node (ref "C37") (pin "2") (pinfunction "2_2") (pintype "passive"))
      (node (ref "M2") (pin "2") (pinfunction "2_2") (pintype "passive"))
      (node (ref "Q2") (pin "3") (pinfunction "D_3") (pintype "passive"))
    )
    (net (code "38") (name "Net-(Q2-G)") (class "Default")
      (node (ref "Q2") (pin "1") (pinfunction "G_1") (pintype "passive"))
      (node (ref "R14") (pin "2") (pinfunction "2_2") (pintype "passive"))
      (node (ref "R15") (pin "2") (pinfunction "2_2") (pintype "passive"))
    )
    (net (code "39") (name "Net-(Q3-D)") (class "Default")
      (node (ref "C38") (pin "2") (pinfunction "2_2") (pintype "passive"))
      (node (ref "M3") (pin "2") (pinfunction "2_2") (pintype "passive"))
      (node (ref "Q3") (pin "3") (pinfunction "D_3") (pintype "passive"))
    )
    (net (code "40") (name "Net-(Q3-G)") (class "Default")
      (node (ref "Q3") (pin "1") (pinfunction "G_1") (pintype "passive"))
      (node (ref "R16") (pin "2") (pinfunction "2_2") (pintype "passive"))
      (node (ref "R17") (pin "2") (pinfunction "2_2") (pintype "passive"))
    )
    (net (code "41") (name "Net-(Q4-D)") (class "Default")
      (node (ref "C39") (pin "2") (pinfunction "2_2") (pintype "passive"))
      (node (ref "M4") (pin "2") (pinfunction "2_2") (pintype "passive"))
      (node (ref "Q4") (pin "3") (pinfunction "D_3") (pintype "passive"))
    )
    (net (code "42") (name "Net-(Q4-G)") (class "Default")
      (node (ref "Q4") (pin "1") (pinfunction "G_1") (pintype "passive"))
      (node (ref "R18") (pin "2") (pinfunction "2_2") (pintype "passive"))
      (node (ref "R19") (pin "2") (pinfunction "2_2") (pintype "passive"))
    )
    (net (code "43") (name "Net-(U1-OSC_IN{slash}PD0)") (class "Default")
      (node (ref "U1") (pin "5") (pinfunction "OSC_IN/PD0_5") (pintype "input"))
      (node (ref "Y1") (pin "3") (pinfunction "3_3") (pintype "passive"))
    )
    (net (code "44") (name "Net-(U1-OSC_OUT{slash}PD1)") (class "Default")
      (node (ref "U1") (pin "6") (pinfunction "OSC_OUT/PD1_6") (pintype "output"))
      (node (ref "Y1") (pin "1") (pinfunction "1_1") (pintype "passive"))
    )
    (net (code "45") (name "Net-(U1-PB2{slash}BOOT1)") (class "Default")
      (node (ref "R21") (pin "1") (pinfunction "1_1") (pintype "passive"))
      (node (ref "U1") (pin "20") (pinfunction "PB2/BOOT1_20") (pintype "bidirectional"))
    )
    (net (code "46") (name "Net-(U2-C+)") (class "Default")
      (node (ref "C2") (pin "1") (pinfunction "1_1") (pintype "passive"))
      (node (ref "U2") (pin "6") (pinfunction "C+_6") (pintype "passive"))
    )
    (net (code "47") (name "Net-(U2-C-)") (class "Default")
      (node (ref "C2") (pin "2") (pinfunction "2_2") (pintype "passive"))
      (node (ref "U2") (pin "4") (pinfunction "C-_4") (pintype "passive"))
    )
    (net (code "48") (name "Net-(U4-CPOUT)") (class "Default")
      (node (ref "C32") (pin "2") (pinfunction "2_2") (pintype "passive"))
      (node (ref "U4") (pin "20") (pinfunction "CPOUT_20") (pintype "passive"))
    )
    (net (code "49") (name "Net-(U4-FSYNC)") (class "Default")
      (node (ref "R20") (pin "2") (pinfunction "2_2") (pintype "passive"))
      (node (ref "U4") (pin "11") (pinfunction "FSYNC_11") (pintype "passive"))
    )
    (net (code "50") (name "Net-(U4-REGOUT)") (class "Default")
      (node (ref "C35") (pin "1") (pinfunction "1_1") (pintype "passive"))
      (node (ref "U4") (pin "10") (pinfunction "REGOUT_10") (pintype "passive"))
    )
    (net (code "51") (name "Net-(U6-ANT1)") (class "Default")
      (node (ref "L2") (pin "2") (pinfunction "2_2") (pintype "passive"))
      (node (ref "L3") (pin "2") (pinfunction "2_2") (pintype "passive"))
      (node (ref "U6") (pin "12") (pinfunction "ANT1_12") (pintype "passive"))
    )
    (net (code "52") (name "Net-(U6-ANT2)") (class "Default")
      (node (ref "L2") (pin "1") (pinfunction "1_1") (pintype "passive"))
      (node (ref "L4") (pin "1") (pinfunction "1_1") (pintype "passive"))
      (node (ref "U6") (pin "13") (pinfunction "ANT2_13") (pintype "passive"))
    )
    (net (code "53") (name "Net-(U6-DVDD)") (class "Default")
      (node (ref "C24") (pin "1") (pinfunction "1_1") (pintype "passive"))
      (node (ref "U6") (pin "19") (pinfunction "DVDD_19") (pintype "passive"))
    )
    (net (code "54") (name "Net-(U6-IREF)") (class "Default")
      (node (ref "R22") (pin "2") (pinfunction "2_2") (pintype "passive"))
      (node (ref "U6") (pin "16") (pinfunction "IREF_16") (pintype "passive"))
    )
    (net (code "55") (name "Net-(U6-VDD_PA)") (class "Default")
      (node (ref "C26") (pin "1") (pinfunction "1_1") (pintype "passive"))
      (node (ref "C27") (pin "1") (pinfunction "1_1") (pintype "passive"))
      (node (ref "L3") (pin "1") (pinfunction "1_1") (pintype "passive"))
      (node (ref "U6") (pin "11") (pinfunction "VDD_PA_11") (pintype "passive"))
    )
    (net (code "56") (name "Net-(U6-XC1)") (class "Default")
      (node (ref "C30") (pin "2") (pinfunction "2_2") (pintype "passive"))
      (node (ref "U6") (pin "10") (pinfunction "XC1_10") (pintype "passive"))
      (node (ref "X2") (pin "3") (pinfunction "3_3") (pintype "passive"))
    )
    (net (code "57") (name "Net-(U6-XC2)") (class "Default")
      (node (ref "C29") (pin "2") (pinfunction "2_2") (pintype "passive"))
      (node (ref "U6") (pin "9") (pinfunction "XC2_9") (pintype "passive"))
      (node (ref "X2") (pin "1") (pinfunction "1_1") (pintype "passive"))
    )
    (net (code "58") (name "RF_3.3V") (class "Default")
      (node (ref "C22") (pin "2") (pinfunction "2_2") (pintype "passive"))
      (node (ref "C23") (pin "2") (pinfunction "2_2") (pintype "passive"))
      (node (ref "R9") (pin "1") (pinfunction "1_1") (pintype "passive"))
      (node (ref "U6") (pin "15") (pinfunction "VDD_15") (pintype "passive"))
      (node (ref "U6") (pin "18") (pinfunction "VDD_18") (pintype "passive"))
      (node (ref "U6") (pin "7") (pinfunction "VDD_7") (pintype "passive"))
    )
    (net (code "59") (name "RF_GND") (class "Default")
      (node (ref "C22") (pin "1") (pinfunction "1_1") (pintype "passive"))
      (node (ref "C23") (pin "1") (pinfunction "1_1") (pintype "passive"))
      (node (ref "C24") (pin "2") (pinfunction "2_2") (pintype "passive"))
      (node (ref "C26") (pin "2") (pinfunction "2_2") (pintype "passive"))
      (node (ref "C27") (pin "2") (pinfunction "2_2") (pintype "passive"))
      (node (ref "C28") (pin "1") (pinfunction "1_1") (pintype "passive"))
      (node (ref "C29") (pin "1") (pinfunction "1_1") (pintype "passive"))
      (node (ref "C30") (pin "1") (pinfunction "1_1") (pintype "passive"))
      (node (ref "R22") (pin "1") (pinfunction "1_1") (pintype "passive"))
      (node (ref "R8") (pin "1") (pinfunction "1_1") (pintype "passive"))
      (node (ref "U6") (pin "14") (pinfunction "VSS_14") (pintype "passive"))
      (node (ref "U6") (pin "17") (pinfunction "VSS_17") (pintype "passive"))
      (node (ref "U6") (pin "20") (pinfunction "VSS_20") (pintype "passive"))
      (node (ref "U6") (pin "8") (pinfunction "VSS_8") (pintype "passive"))
    )
    (net (code "60") (name "VBAT") (class "Default")
      (node (ref "C1") (pin "2") (pinfunction "2_2") (pintype "passive"))
      (node (ref "C36") (pin "1") (pinfunction "1_1") (pintype "passive"))
      (node (ref "C37") (pin "1") (pinfunction "1_1") (pintype "passive"))
      (node (ref "C38") (pin "1") (pinfunction "1_1") (pintype "passive"))
      (node (ref "C39") (pin "1") (pinfunction "1_1") (pintype "passive"))
      (node (ref "M1") (pin "1") (pinfunction "1_1") (pintype "passive"))
      (node (ref "M2") (pin "1") (pinfunction "1_1") (pintype "passive"))
      (node (ref "M3") (pin "1") (pinfunction "1_1") (pintype "passive"))
      (node (ref "M4") (pin "1") (pinfunction "1_1") (pintype "passive"))
      (node (ref "R6") (pin "1") (pinfunction "1_1") (pintype "passive"))
      (node (ref "S1") (pin "2") (pinfunction "2_2") (pintype "passive"))
      (node (ref "U2") (pin "3") (pinfunction "EN_3") (pintype "passive"))
      (node (ref "U2") (pin "5") (pinfunction "VIN_5") (pintype "passive"))
    )
    (net (code "61") (name "unconnected-(D7-DO-Pad2)") (class "Default")
      (node (ref "D7") (pin "2") (pinfunction "DO_2") (pintype "passive"))
    )
    (net (code "62") (name "unconnected-(S1-Pad3)") (class "Default")
      (node (ref "S1") (pin "3") (pinfunction "3_3") (pintype "passive+no_connect"))
    )
    (net (code "63") (name "unconnected-(U1-PA0-WKUP-Pad10)") (class "Default")
      (node (ref "U1") (pin "10") (pinfunction "PA0-WKUP_10") (pintype "bidirectional"))
    )
    (net (code "64") (name "unconnected-(U1-PA2-Pad12)") (class "Default")
      (node (ref "U1") (pin "12") (pinfunction "PA2_12") (pintype "bidirectional"))
    )
    (net (code "65") (name "unconnected-(U1-PA5-Pad15)") (class "Default")
      (node (ref "U1") (pin "15") (pinfunction "PA5_15") (pintype "bidirectional"))
    )
    (net (code "66") (name "unconnected-(U1-PA8-Pad29)") (class "Default")
      (node (ref "U1") (pin "29") (pinfunction "PA8_29") (pintype "bidirectional"))
    )
    (net (code "67") (name "unconnected-(U1-PA15{slash}JTDI-Pad38)") (class "Default")
      (node (ref "U1") (pin "38") (pinfunction "PA15/JTDI_38") (pintype "bidirectional"))
    )
    (net (code "68") (name "unconnected-(U1-PB4{slash}JNTRST-Pad40)") (class "Default")
      (node (ref "U1") (pin "40") (pinfunction "PB4/JNTRST_40") (pintype "bidirectional"))
    )
    (net (code "69") (name "unconnected-(U1-PB5-Pad41)") (class "Default")
      (node (ref "U1") (pin "41") (pinfunction "PB5_41") (pintype "bidirectional"))
    )
    (net (code "70") (name "unconnected-(U1-PB8-Pad45)") (class "Default")
      (node (ref "U1") (pin "45") (pinfunction "PB8_45") (pintype "bidirectional"))
    )
    (net (code "71") (name "unconnected-(U1-PB9-Pad46)") (class "Default")
      (node (ref "U1") (pin "46") (pinfunction "PB9_46") (pintype "bidirectional"))
    )
    (net (code "72") (name "unconnected-(U1-PB10-Pad21)") (class "Default")
      (node (ref "U1") (pin "21") (pinfunction "PB10_21") (pintype "bidirectional"))
    )
    (net (code "73") (name "unconnected-(U1-PB11-Pad22)") (class "Default")
      (node (ref "U1") (pin "22") (pinfunction "PB11_22") (pintype "bidirectional"))
    )
    (net (code "74") (name "unconnected-(U1-PC13-TAMPER-RTC-Pad2)") (class "Default")
      (node (ref "U1") (pin "2") (pinfunction "PC13-TAMPER-RTC_2") (pintype "bidirectional"))
    )
    (net (code "75") (name "unconnected-(U1-PC14-OSC32_IN-Pad3)") (class "Default")
      (node (ref "U1") (pin "3") (pinfunction "PC14-OSC32_IN_3") (pintype "bidirectional"))
    )
    (net (code "76") (name "unconnected-(U1-PC15-OSC32_OUT-Pad4)") (class "Default")
      (node (ref "U1") (pin "4") (pinfunction "PC15-OSC32_OUT_4") (pintype "bidirectional"))
    )
    (net (code "77") (name "unconnected-(U4-A-CL-Pad7)") (class "Default")
      (node (ref "U4") (pin "7") (pinfunction "A-CL_7") (pintype "passive+no_connect"))
    )
    (net (code "78") (name "unconnected-(U4-A_DA-Pad6)") (class "Default")
      (node (ref "U4") (pin "6") (pinfunction "A_DA_6") (pintype "passive+no_connect"))
    )
    (net (code "79") (name "unconnected-(U4-CLKOUT-Pad22)") (class "Default")
      (node (ref "U4") (pin "22") (pinfunction "CLKOUT_22") (pintype "passive+no_connect"))
    )
    (net (code "80") (name "unconnected-(U4-NC-Pad2)") (class "Default")
      (node (ref "U4") (pin "2") (pinfunction "NC_2") (pintype "passive+no_connect"))
    )
    (net (code "81") (name "unconnected-(U4-NC-Pad3)") (class "Default")
      (node (ref "U4") (pin "3") (pinfunction "NC_3") (pintype "passive+no_connect"))
    )
    (net (code "82") (name "unconnected-(U4-NC-Pad4)") (class "Default")
      (node (ref "U4") (pin "4") (pinfunction "NC_4") (pintype "passive+no_connect"))
    )
    (net (code "83") (name "unconnected-(U4-NC-Pad5)") (class "Default")
      (node (ref "U4") (pin "5") (pinfunction "NC_5") (pintype "passive+no_connect"))
    )
    (net (code "84") (name "unconnected-(U4-NC-Pad14)") (class "Default")
      (node (ref "U4") (pin "14") (pinfunction "NC_14") (pintype "passive+no_connect"))
    )
    (net (code "85") (name "unconnected-(U4-NC-Pad15)") (class "Default")
      (node (ref "U4") (pin "15") (pinfunction "NC_15") (pintype "passive+no_connect"))
    )
    (net (code "86") (name "unconnected-(U4-NC-Pad16)") (class "Default")
      (node (ref "U4") (pin "16") (pinfunction "NC_16") (pintype "passive+no_connect"))
    )
    (net (code "87") (name "unconnected-(U4-NC-Pad17)") (class "Default")
      (node (ref "U4") (pin "17") (pinfunction "NC_17") (pintype "passive+no_connect"))
    )
    (net (code "88") (name "unconnected-(U4-RESV-Pad19)") (class "Default")
      (node (ref "U4") (pin "19") (pinfunction "RESV_19") (pintype "passive+no_connect"))
    )
    (net (code "89") (name "unconnected-(U4-RESV-Pad21)") (class "Default")
      (node (ref "U4") (pin "21") (pinfunction "RESV_21") (pintype "passive+no_connect"))
    )
    (net (code "90") (name "unconnected-(X2-GND-Pad2)") (class "Default")
      (node (ref "X2") (pin "2") (pinfunction "GND_2") (pintype "passive+no_connect"))
    )
    (net (code "91") (name "unconnected-(X2-GND-Pad4)") (class "Default")
      (node (ref "X2") (pin "4") (pinfunction "GND_4") (pintype "passive+no_connect"))
    )
  )
)
